# BQ32KSCH.net
KiCad netlist of a schematic drawn in EAGLE
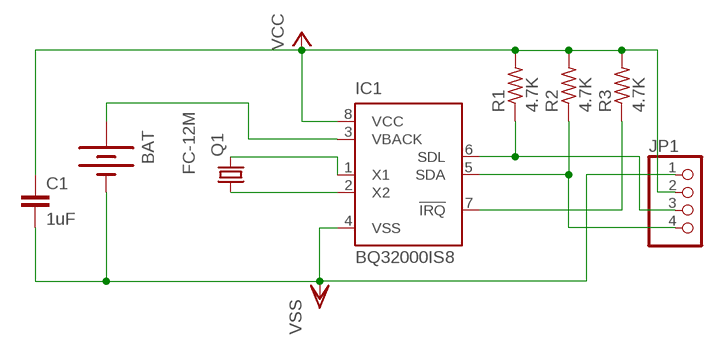
[diagram p0: schematic, sheet 1]

(export (version "E")
  (design (tool "Eeschema 10.0.6"))
  (components
    (comp (ref "BAT")
      (value "CR1025-HOLDER")
      (footprint "eagle-import:CR1025-HOLDER")
      (libsource (lib "eagle-import") (part "CR1025-HOLDER"))
    )
    (comp (ref "C1")
      (value "1uF")
      (footprint "eagle-import:C3216")
      (libsource (lib "eagle-import") (part "C-EUC3216"))
    )
    (comp (ref "IC1")
      (value "BQ32000IS8")
      (footprint "eagle-import:SO-08")
      (libsource (lib "eagle-import") (part "BQ32000S8I"))
    )
    (comp (ref "JP1")
      (value "PINHD-1X4")
      (footprint "eagle-import:1X04")
      (libsource (lib "eagle-import") (part "PINHD-1X4"))
    )
    (comp (ref "Q1")
      (value "FC-12M")
      (footprint "eagle-import:FC-12M")
      (libsource (lib "eagle-import") (part "FC-12M"))
    )
    (comp (ref "R1")
      (value "4.7K")
      (footprint "eagle-import:R0402")
      (libsource (lib "eagle-import") (part "R-US_R0402"))
    )
    (comp (ref "R2")
      (value "4.7K")
      (footprint "eagle-import:R0402")
      (libsource (lib "eagle-import") (part "R-US_R0402"))
    )
    (comp (ref "R3")
      (value "4.7K")
      (footprint "eagle-import:R0402")
      (libsource (lib "eagle-import") (part "R-US_R0402"))
    )
  )
  (nets
    (net (code "1") (name "Net-(IC1-SDA)") (class "Default")
      (node (ref "IC1") (pin "5") (pinfunction "SDA_5") (pintype "bidirectional"))
      (node (ref "JP1") (pin "4") (pinfunction "4_4") (pintype "passive"))
      (node (ref "R2") (pin "1") (pinfunction "1_1") (pintype "passive"))
    )
    (net (code "2") (name "Net-(IC1-SDL)") (class "Default")
      (node (ref "IC1") (pin "6") (pinfunction "SDL_6") (pintype "input"))
      (node (ref "JP1") (pin "3") (pinfunction "3_3") (pintype "passive"))
      (node (ref "R1") (pin "1") (pinfunction "1_1") (pintype "passive"))
    )
    (net (code "3") (name "Net-(IC1-VBACK)") (class "Default")
      (node (ref "BAT") (pin "PRWP1") (pinfunction "PWRP_PRWP1") (pintype "power_in"))
      (node (ref "BAT") (pin "PWRP2") (pinfunction "PWRP_PWRP2") (pintype "power_in"))
      (node (ref "IC1") (pin "3") (pinfunction "VBACK_3") (pintype "input"))
    )
    (net (code "4") (name "Net-(IC1-X1)") (class "Default")
      (node (ref "IC1") (pin "1") (pinfunction "X1_1") (pintype "input"))
      (node (ref "Q1") (pin "2") (pinfunction "2_2") (pintype "passive"))
    )
    (net (code "5") (name "Net-(IC1-X2)") (class "Default")
      (node (ref "IC1") (pin "2") (pinfunction "X2_2") (pintype "output"))
      (node (ref "Q1") (pin "1") (pinfunction "1_1") (pintype "passive"))
    )
    (net (code "6") (name "Net-(IC1-~{IRQ})") (class "Default")
      (node (ref "IC1") (pin "7") (pinfunction "~{IRQ}_7") (pintype "output"))
      (node (ref "R3") (pin "1") (pinfunction "1_1") (pintype "passive"))
    )
    (net (code "7") (name "VCC") (class "Default")
      (node (ref "C1") (pin "1") (pinfunction "1_1") (pintype "passive"))
      (node (ref "IC1") (pin "8") (pinfunction "VCC_8") (pintype "power_in"))
      (node (ref "JP1") (pin "2") (pinfunction "2_2") (pintype "passive"))
      (node (ref "R1") (pin "2") (pinfunction "2_2") (pintype "passive"))
      (node (ref "R2") (pin "2") (pinfunction "2_2") (pintype "passive"))
      (node (ref "R3") (pin "2") (pinfunction "2_2") (pintype "passive"))
    )
    (net (code "8") (name "VSS") (class "Default")
      (node (ref "BAT") (pin "PWRM1") (pinfunction "PWRM_PWRM1") (pintype "power_in"))
      (node (ref "BAT") (pin "PWRM2") (pinfunction "PWRM_PWRM2") (pintype "power_in"))
      (node (ref "C1") (pin "2") (pinfunction "2_2") (pintype "passive"))
      (node (ref "IC1") (pin "4") (pinfunction "VSS_4") (pintype "power_in"))
      (node (ref "JP1") (pin "1") (pinfunction "1_1") (pintype "passive"))
    )
  )
)
